# lm317.net
KiCad netlist of a schematic drawn in EAGLE
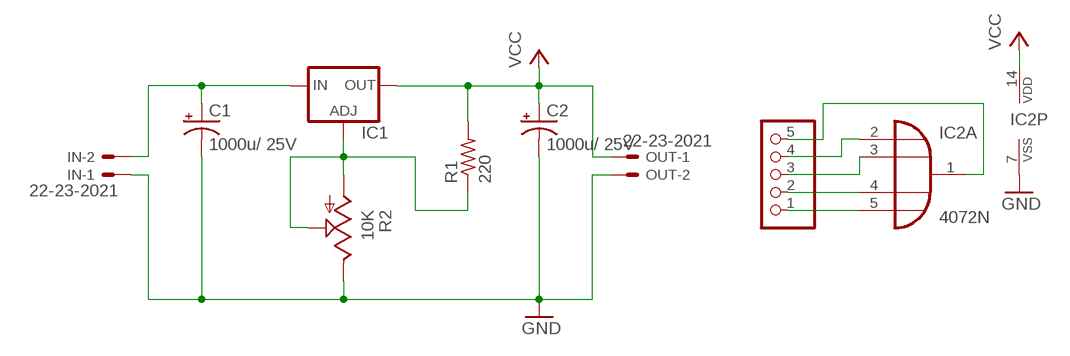
[diagram p0: schematic, sheet 1]

(export (version "E")
  (design (tool "Eeschema 10.0.6"))
  (components
    (comp (ref "C1")
      (value "1000u/ 25V")
      (footprint "eagle-import:E5-8,5")
      (libsource (lib "eagle-import") (part "CPOL-USE5-8.5"))
    )
    (comp (ref "C2")
      (value "1000u/ 25V")
      (footprint "eagle-import:E5-8,5")
      (libsource (lib "eagle-import") (part "CPOL-USE5-8.5"))
    )
    (comp (ref "IC1")
      (value "LM317TS")
      (footprint "eagle-import:317TS")
      (libsource (lib "eagle-import") (part "LM317TS"))
    )
    (comp (ref "IC2")
      (value "4072N")
      (footprint "eagle-import:DIL14")
      (libsource (lib "eagle-import") (part "4072N"))
    )
    (comp (ref "IN")
      (value "22-23-2021")
      (footprint "eagle-import:22-23-2021")
      (fields (field (name "MF") "MOLEX"))
      (libsource (lib "eagle-import") (part "22-23-2021"))
    )
    (comp (ref "JP1")
      (value "PINHD-1X5")
      (footprint "eagle-import:1X05")
      (libsource (lib "eagle-import") (part "PINHD-1X5"))
    )
    (comp (ref "OUT")
      (value "22-23-2021")
      (footprint "eagle-import:22-23-2021")
      (fields (field (name "MF") "MOLEX"))
      (libsource (lib "eagle-import") (part "22-23-2021"))
    )
    (comp (ref "R1")
      (value "220")
      (footprint "eagle-import:0207_10")
      (libsource (lib "eagle-import") (part "R-US_0207/10"))
    )
    (comp (ref "R2")
      (value "10K")
      (footprint "eagle-import:CA6V")
      (libsource (lib "eagle-import") (part "TRIM_US-CA6V"))
    )
  )
  (nets
    (net (code "1") (name "GND") (class "Default")
      (node (ref "C1") (pin "-") (pinfunction "-_-") (pintype "passive"))
      (node (ref "C2") (pin "-") (pinfunction "-_-") (pintype "passive"))
      (node (ref "IC2") (pin "7") (pinfunction "VSS_7") (pintype "power_in"))
      (node (ref "IN") (pin "1") (pinfunction "S_1") (pintype "passive"))
      (node (ref "OUT") (pin "2") (pinfunction "S_2") (pintype "passive"))
      (node (ref "R2") (pin "E") (pinfunction "E_E") (pintype "passive"))
    )
    (net (code "2") (name "Net-(IC1-ADJ)") (class "Default")
      (node (ref "IC1") (pin "1") (pinfunction "ADJ_1") (pintype "input"))
      (node (ref "R1") (pin "1") (pinfunction "1_1") (pintype "passive"))
      (node (ref "R2") (pin "A") (pinfunction "A_A") (pintype "passive"))
      (node (ref "R2") (pin "S") (pinfunction "S_S") (pintype "passive"))
    )
    (net (code "3") (name "Net-(IC1-IN)") (class "Default")
      (node (ref "C1") (pin "+") (pinfunction "+_+") (pintype "passive"))
      (node (ref "IC1") (pin "3") (pinfunction "IN_3") (pintype "input"))
      (node (ref "IN") (pin "2") (pinfunction "S_2") (pintype "passive"))
    )
    (net (code "4") (name "Net-(IC2A-I0)") (class "Default")
      (node (ref "IC2") (pin "2") (pinfunction "I0_2") (pintype "input"))
      (node (ref "JP1") (pin "4") (pinfunction "4_4") (pintype "passive"))
    )
    (net (code "5") (name "Net-(IC2A-I1)") (class "Default")
      (node (ref "IC2") (pin "3") (pinfunction "I1_3") (pintype "input"))
      (node (ref "JP1") (pin "3") (pinfunction "3_3") (pintype "passive"))
    )
    (net (code "6") (name "Net-(IC2A-I2)") (class "Default")
      (node (ref "IC2") (pin "4") (pinfunction "I2_4") (pintype "input"))
      (node (ref "JP1") (pin "2") (pinfunction "2_2") (pintype "passive"))
    )
    (net (code "7") (name "Net-(IC2A-I3)") (class "Default")
      (node (ref "IC2") (pin "5") (pinfunction "I3_5") (pintype "input"))
      (node (ref "JP1") (pin "1") (pinfunction "1_1") (pintype "passive"))
    )
    (net (code "8") (name "Net-(IC2A-O)") (class "Default")
      (node (ref "IC2") (pin "1") (pinfunction "O_1") (pintype "output"))
      (node (ref "JP1") (pin "5") (pinfunction "5_5") (pintype "passive"))
    )
    (net (code "9") (name "VCC") (class "Default")
      (node (ref "C2") (pin "+") (pinfunction "+_+") (pintype "passive"))
      (node (ref "IC1") (pin "2") (pinfunction "OUT_2") (pintype "passive"))
      (node (ref "IC2") (pin "14") (pinfunction "VDD_14") (pintype "power_in"))
      (node (ref "OUT") (pin "1") (pinfunction "S_1") (pintype "passive"))
      (node (ref "R1") (pin "2") (pinfunction "2_2") (pintype "passive"))
    )
  )
)
